# weaver_groveph.net
KiCad netlist of a schematic drawn in EAGLE
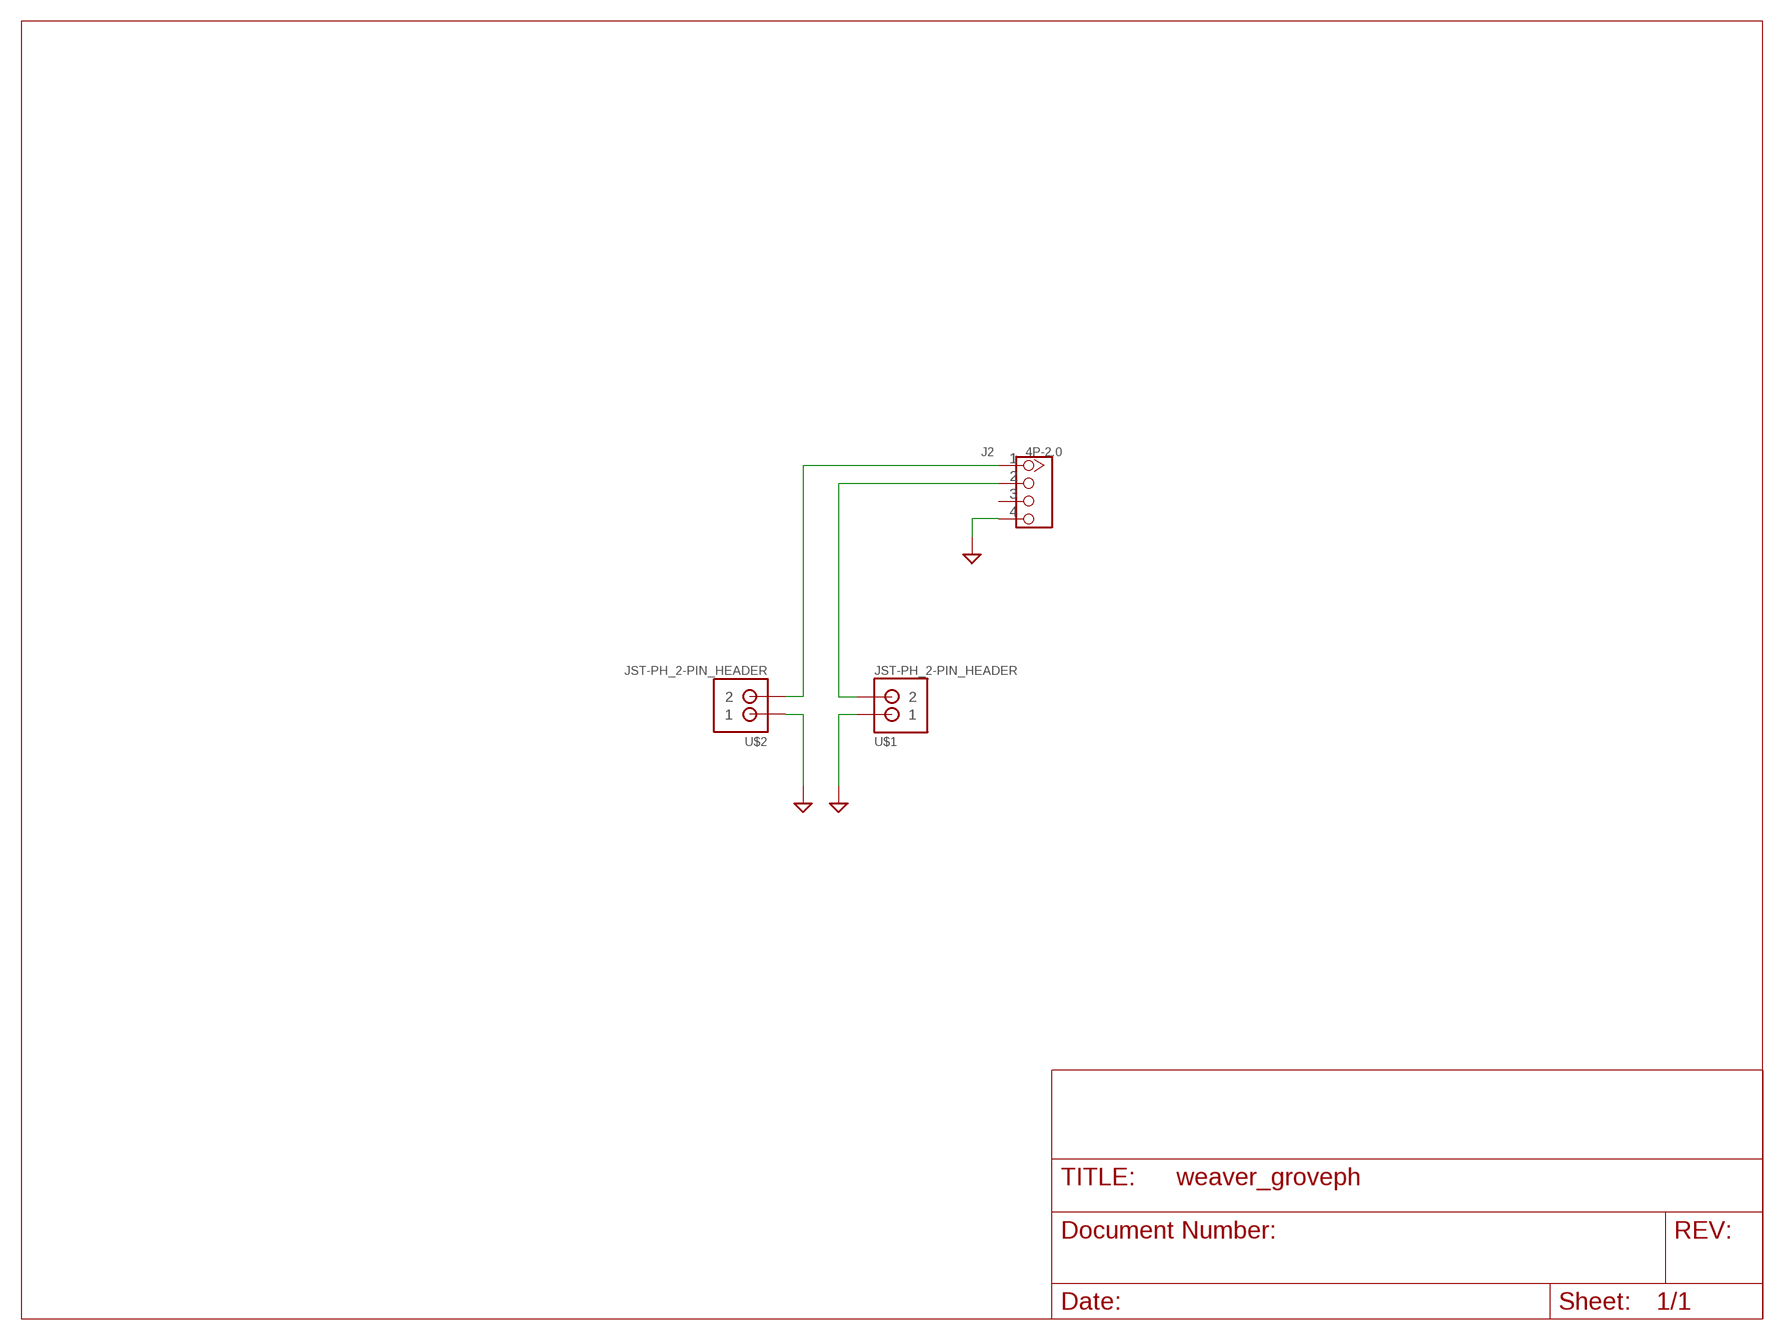
[diagram p0: schematic, sheet 1]

(export (version "E")
  (design (tool "Eeschema 10.0.6"))
  (components
    (comp (ref "J2")
      (value "4P-2.0")
      (footprint "eagle-import:HW4-2.0")
      (libsource (lib "eagle-import") (part "GROVE-CONNECTOR-DIP(4P-2.0)"))
    )
    (comp (ref "U$1")
      (value "JST-PH_2-PIN_HEADER")
      (footprint "eagle-import:JST_B2B-PH_HEADER")
      (libsource (lib "eagle-import") (part "JST-PH_2-PIN_HEADER"))
    )
    (comp (ref "U$2")
      (value "JST-PH_2-PIN_HEADER")
      (footprint "eagle-import:JST_B2B-PH_HEADER")
      (libsource (lib "eagle-import") (part "JST-PH_2-PIN_HEADER"))
    )
  )
  (nets
    (net (code "1") (name "GND") (class "Default")
      (node (ref "J2") (pin "4") (pinfunction "4_4") (pintype "bidirectional"))
      (node (ref "U$1") (pin "P1") (pinfunction "1_P1") (pintype "bidirectional"))
      (node (ref "U$2") (pin "P1") (pinfunction "1_P1") (pintype "bidirectional"))
    )
    (net (code "2") (name "Net-(U$1-2)") (class "Default")
      (node (ref "J2") (pin "2") (pinfunction "2_2") (pintype "bidirectional"))
      (node (ref "U$1") (pin "P2") (pinfunction "2_P2") (pintype "bidirectional"))
    )
    (net (code "3") (name "Net-(U$2-2)") (class "Default")
      (node (ref "J2") (pin "1") (pinfunction "1_1") (pintype "bidirectional"))
      (node (ref "U$2") (pin "P2") (pinfunction "2_P2") (pintype "bidirectional"))
    )
    (net (code "4") (name "unconnected-(J2-Pad3)") (class "Default")
      (node (ref "J2") (pin "3") (pinfunction "3_3") (pintype "bidirectional"))
    )
  )
)
